# Controller-Board_Rack-PDU_2_0.net
KiCad netlist of a schematic drawn in EAGLE
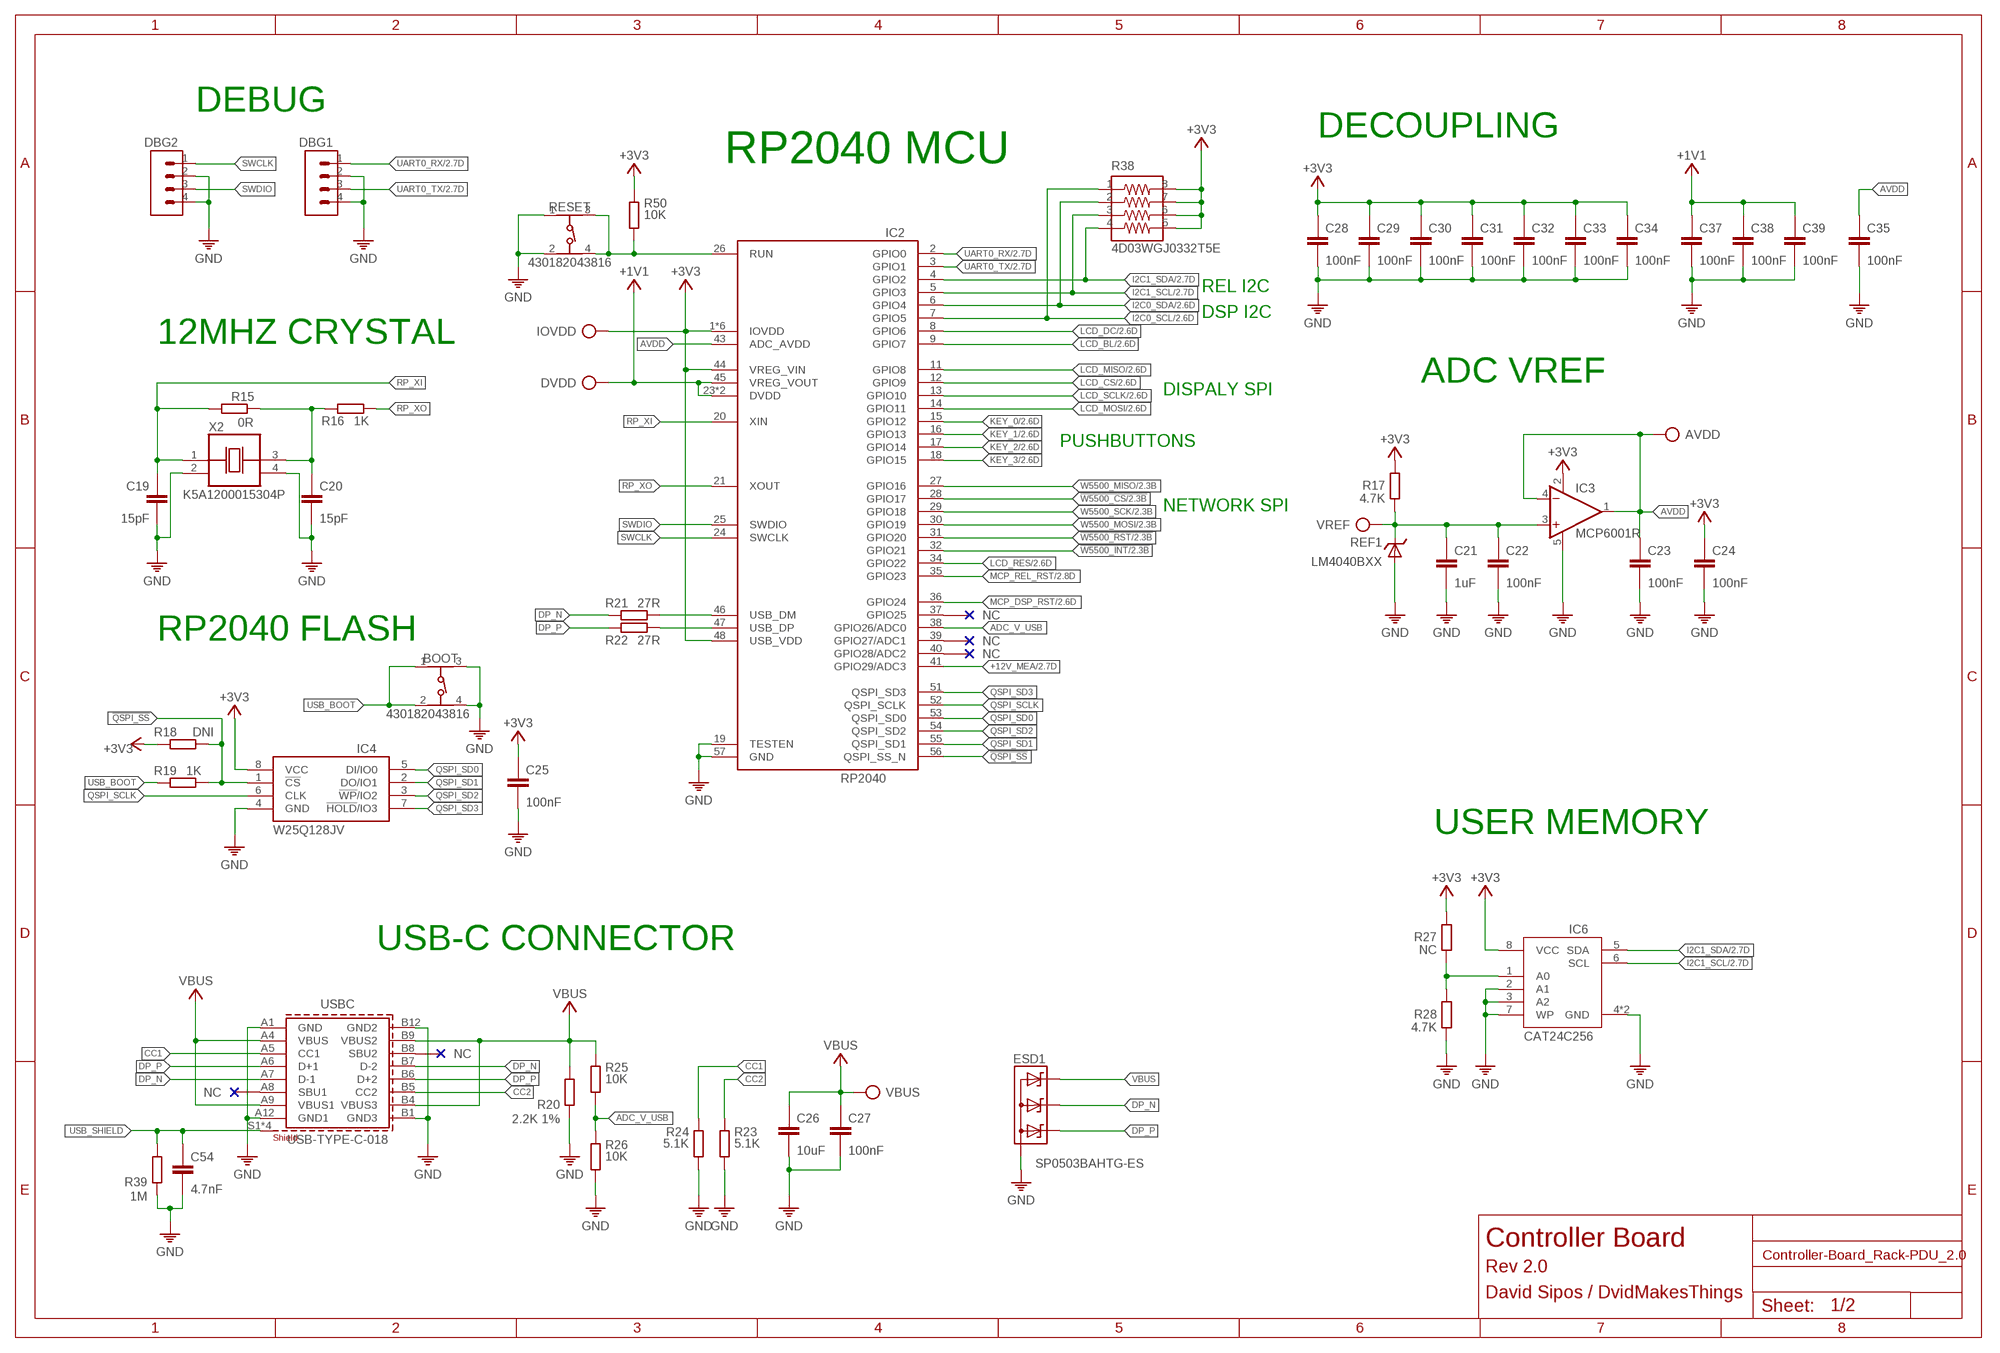
[diagram p0: schematic, sheet 1]
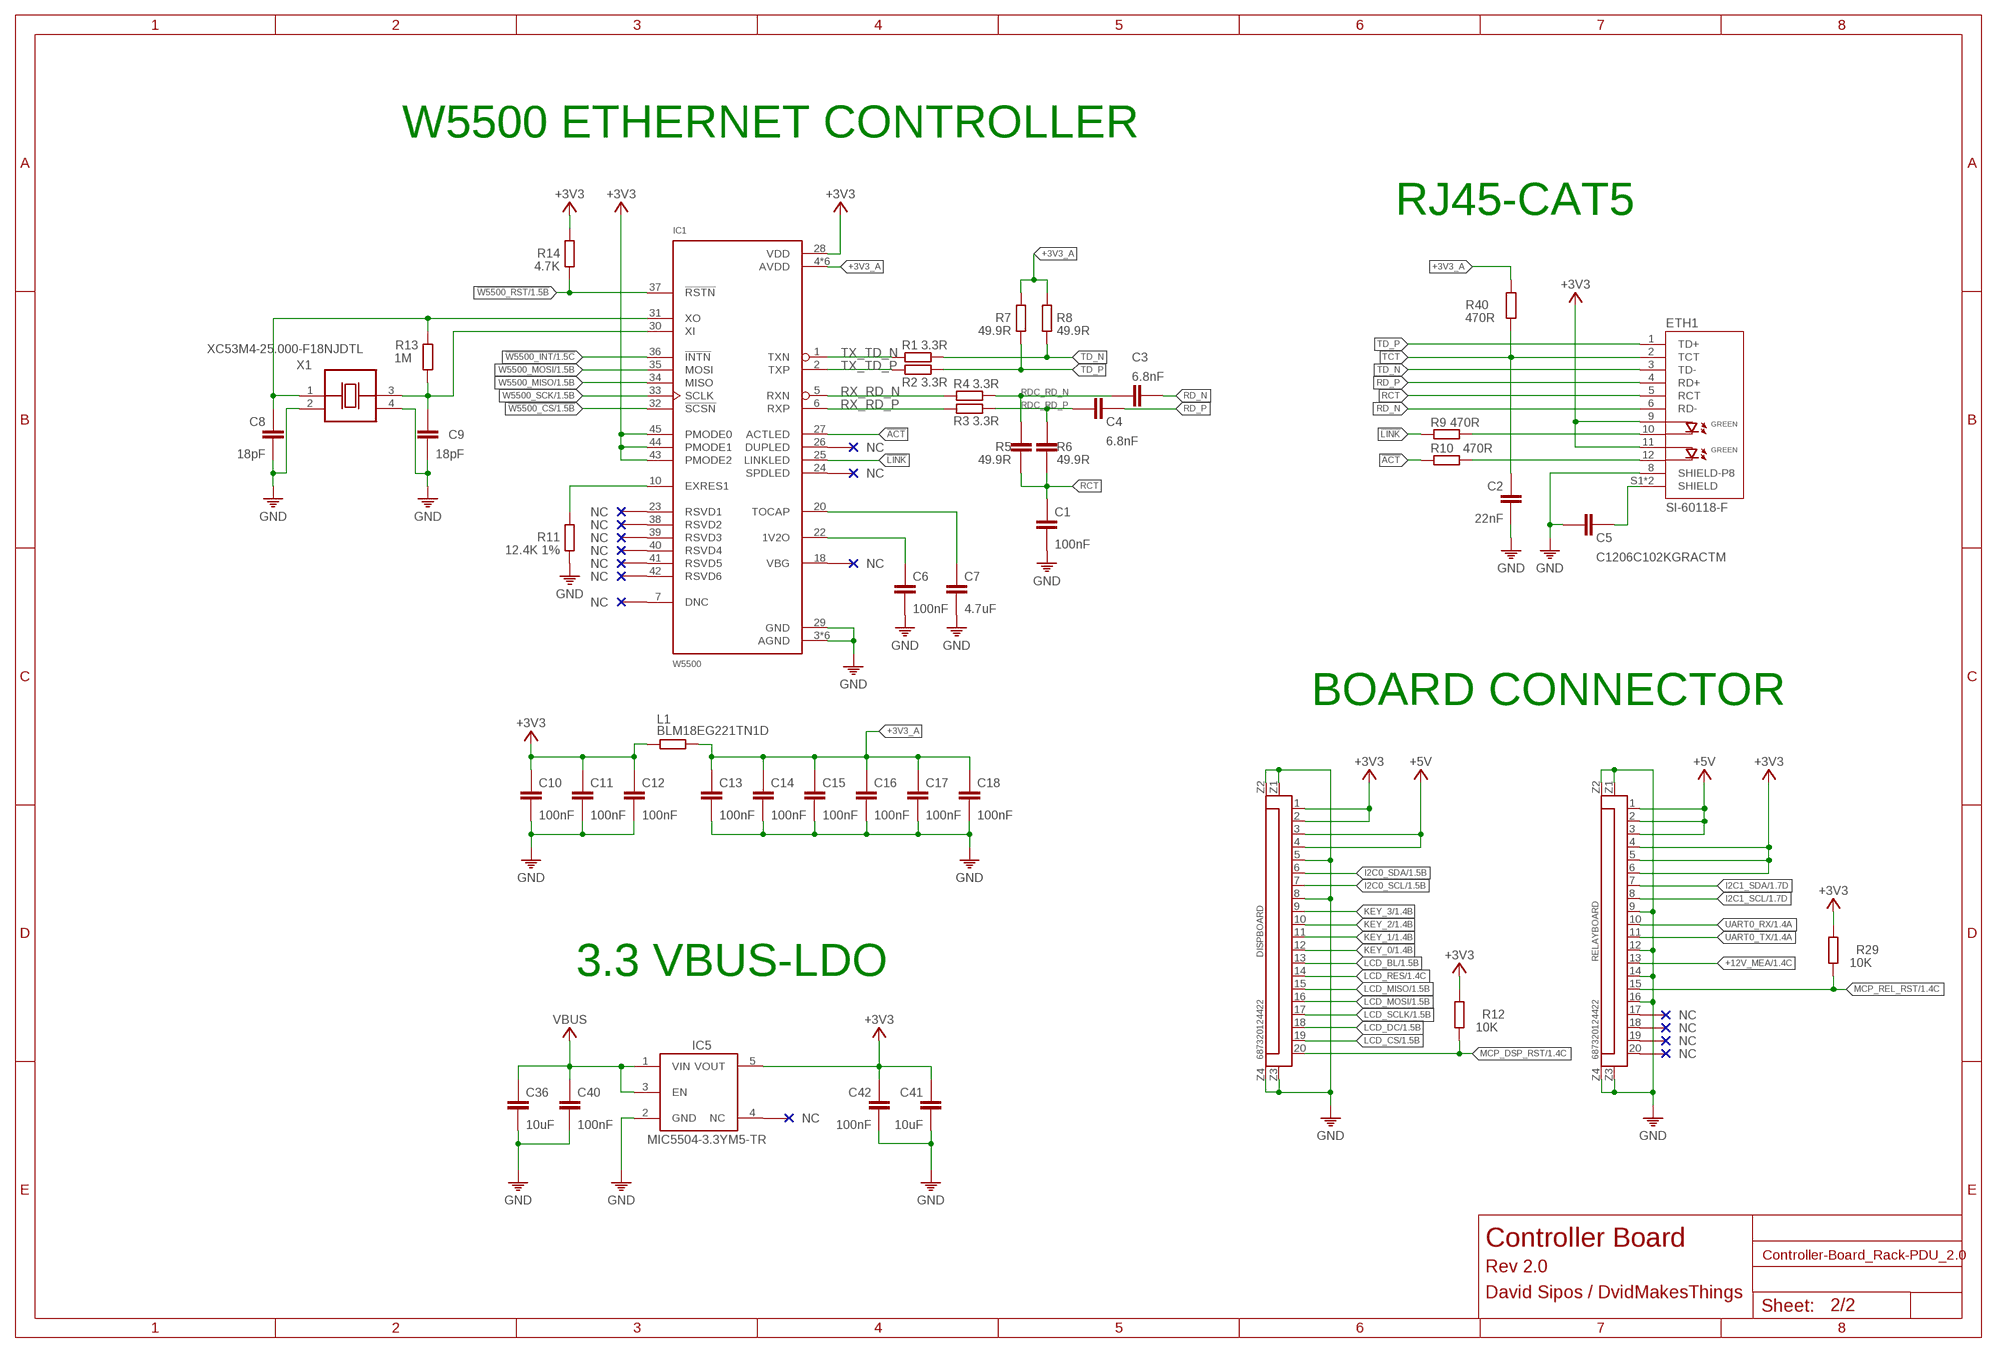
[diagram p1: schematic, sheet 2]

(export (version "E")
  (design (tool "Eeschema 10.0.6"))
  (components
    (comp (ref "AVDD")
      (value "TP")
      (footprint "eagle-import:TP")
      (libsource (lib "eagle-import") (part "TP"))
    )
    (comp (ref "BOOT")
      (value "430182043816")
      (footprint "eagle-import:430182043816")
      (libsource (lib "eagle-import") (part "430182043816"))
    )
    (comp (ref "C19")
      (value "15pF")
      (footprint "eagle-import:C0402")
      (libsource (lib "eagle-import") (part "C-0402"))
    )
    (comp (ref "C20")
      (value "15pF")
      (footprint "eagle-import:C0402")
      (libsource (lib "eagle-import") (part "C-0402"))
    )
    (comp (ref "C21")
      (value "1uF")
      (footprint "eagle-import:C0402")
      (libsource (lib "eagle-import") (part "C-0402"))
    )
    (comp (ref "C22")
      (value "100nF")
      (footprint "eagle-import:C0402")
      (libsource (lib "eagle-import") (part "C-0402"))
    )
    (comp (ref "C23")
      (value "100nF")
      (footprint "eagle-import:C0402")
      (libsource (lib "eagle-import") (part "C-0402"))
    )
    (comp (ref "C24")
      (value "100nF")
      (footprint "eagle-import:C0402")
      (libsource (lib "eagle-import") (part "C-0402"))
    )
    (comp (ref "C25")
      (value "100nF")
      (footprint "eagle-import:C0402")
      (libsource (lib "eagle-import") (part "C-0402"))
    )
    (comp (ref "C26")
      (value "10uF")
      (footprint "eagle-import:0805")
      (libsource (lib "eagle-import") (part "C0805"))
    )
    (comp (ref "C27")
      (value "100nF")
      (footprint "eagle-import:0402")
      (libsource (lib "eagle-import") (part "C0402"))
    )
    (comp (ref "C28")
      (value "100nF")
      (footprint "eagle-import:C0402")
      (libsource (lib "eagle-import") (part "C-0402"))
    )
    (comp (ref "C29")
      (value "100nF")
      (footprint "eagle-import:C0402")
      (libsource (lib "eagle-import") (part "C-0402"))
    )
    (comp (ref "C30")
      (value "100nF")
      (footprint "eagle-import:C0402")
      (libsource (lib "eagle-import") (part "C-0402"))
    )
    (comp (ref "C31")
      (value "100nF")
      (footprint "eagle-import:C0402")
      (libsource (lib "eagle-import") (part "C-0402"))
    )
    (comp (ref "C32")
      (value "100nF")
      (footprint "eagle-import:C0402")
      (libsource (lib "eagle-import") (part "C-0402"))
    )
    (comp (ref "C33")
      (value "100nF")
      (footprint "eagle-import:C0402")
      (libsource (lib "eagle-import") (part "C-0402"))
    )
    (comp (ref "C34")
      (value "100nF")
      (footprint "eagle-import:C0402")
      (libsource (lib "eagle-import") (part "C-0402"))
    )
    (comp (ref "C35")
      (value "100nF")
      (footprint "eagle-import:C0402")
      (libsource (lib "eagle-import") (part "C-0402"))
    )
    (comp (ref "C37")
      (value "100nF")
      (footprint "eagle-import:C0402")
      (libsource (lib "eagle-import") (part "C-0402"))
    )
    (comp (ref "C38")
      (value "100nF")
      (footprint "eagle-import:C0402")
      (libsource (lib "eagle-import") (part "C-0402"))
    )
    (comp (ref "C39")
      (value "100nF")
      (footprint "eagle-import:C0402")
      (libsource (lib "eagle-import") (part "C-0402"))
    )
    (comp (ref "C54")
      (value "4.7nF")
      (footprint "eagle-import:0402")
      (libsource (lib "eagle-import") (part "C0402"))
    )
    (comp (ref "DBG1")
      (value "CON-1X4")
      (footprint "eagle-import:1X4")
      (libsource (lib "eagle-import") (part "CON-1X4"))
    )
    (comp (ref "DBG2")
      (value "CON-1X4")
      (footprint "eagle-import:1X4")
      (libsource (lib "eagle-import") (part "CON-1X4"))
    )
    (comp (ref "DVDD")
      (value "TP")
      (footprint "eagle-import:TP")
      (libsource (lib "eagle-import") (part "TP"))
    )
    (comp (ref "ESD1")
      (value "SP0503BAHTG-ES")
      (footprint "eagle-import:SOT143")
      (libsource (lib "eagle-import") (part "SP0503BAHT"))
    )
    (comp (ref "IC2")
      (value "RP2040")
      (footprint "eagle-import:QFN40P700X700X100-57T510")
      (libsource (lib "eagle-import") (part "RP2040"))
    )
    (comp (ref "IC3")
      (value "MCP6001R")
      (footprint "eagle-import:SOT23-5")
      (libsource (lib "eagle-import") (part "MCP6001RT"))
    )
    (comp (ref "IC4")
      (value "W25Q128JVPIQ")
      (footprint "eagle-import:SON127P600X500X75-8N")
      (libsource (lib "eagle-import") (part "W25Q128JVP"))
    )
    (comp (ref "IC6")
      (value "CAT24C512HU5IGT3")
      (footprint "eagle-import:SON50P300X200X50-9T130X140N")
      (libsource (lib "eagle-import") (part "CAT24C256-HU4"))
    )
    (comp (ref "IOVDD")
      (value "TP")
      (footprint "eagle-import:TP")
      (libsource (lib "eagle-import") (part "TP"))
    )
    (comp (ref "R15")
      (value "0R")
      (footprint "eagle-import:0402")
      (libsource (lib "eagle-import") (part "R0402"))
    )
    (comp (ref "R16")
      (value "1K")
      (footprint "eagle-import:0402")
      (libsource (lib "eagle-import") (part "R0402"))
    )
    (comp (ref "R17")
      (value "4.7K")
      (footprint "eagle-import:0402")
      (libsource (lib "eagle-import") (part "R0402"))
    )
    (comp (ref "R18")
      (value "DNI")
      (footprint "eagle-import:0402")
      (libsource (lib "eagle-import") (part "R0402"))
    )
    (comp (ref "R19")
      (value "1K")
      (footprint "eagle-import:0402")
      (libsource (lib "eagle-import") (part "R0402"))
    )
    (comp (ref "R20")
      (value "2.2K 1%")
      (footprint "eagle-import:0402")
      (libsource (lib "eagle-import") (part "ds_passive_46685041_R0402"))
    )
    (comp (ref "R21")
      (value "27R")
      (footprint "eagle-import:0402")
      (libsource (lib "eagle-import") (part "R0402"))
    )
    (comp (ref "R22")
      (value "27R")
      (footprint "eagle-import:0402")
      (libsource (lib "eagle-import") (part "R0402"))
    )
    (comp (ref "R23")
      (value "5.1K")
      (footprint "eagle-import:0402")
      (libsource (lib "eagle-import") (part "ds_passive_46685041_R0402"))
    )
    (comp (ref "R24")
      (value "5.1K")
      (footprint "eagle-import:0402")
      (libsource (lib "eagle-import") (part "ds_passive_46685041_R0402"))
    )
    (comp (ref "R25")
      (value "10K")
      (footprint "eagle-import:0402")
      (libsource (lib "eagle-import") (part "ds_passive_46685041_R0402"))
    )
    (comp (ref "R26")
      (value "10K")
      (footprint "eagle-import:0402")
      (libsource (lib "eagle-import") (part "ds_passive_46685041_R0402"))
    )
    (comp (ref "R27")
      (value "NC")
      (footprint "eagle-import:0402")
      (libsource (lib "eagle-import") (part "R0402"))
    )
    (comp (ref "R28")
      (value "4.7K")
      (footprint "eagle-import:0402")
      (libsource (lib "eagle-import") (part "R0402"))
    )
    (comp (ref "R38")
      (value "4D03WGJ0332T5E")
      (footprint "eagle-import:742C083103JP")
      (fields
        (field (name "MANUFACTURER") "CTS Resistor Products")
        (field (name "MPN") "742C083103JP")
        (field (name "CREATED_BY") "PCBLayout.com")
      )
      (libsource (lib "eagle-import") (part "742C083103JP"))
    )
    (comp (ref "R39")
      (value "1M")
      (footprint "eagle-import:0402")
      (libsource (lib "eagle-import") (part "ds_passive_46685041_R0402"))
    )
    (comp (ref "R50")
      (value "10K")
      (footprint "eagle-import:0402")
      (libsource (lib "eagle-import") (part "ds_passive_46685041_R0402"))
    )
    (comp (ref "REF1")
      (value "LM4040BXX")
      (footprint "eagle-import:SOT23")
      (libsource (lib "eagle-import") (part "LM4040BXX"))
    )
    (comp (ref "RESET")
      (value "430182043816")
      (footprint "eagle-import:430182043816")
      (libsource (lib "eagle-import") (part "430182043816"))
    )
    (comp (ref "USBC")
      (value "USB-TYPE-C-018")
      (footprint "eagle-import:629722000214")
      (libsource (lib "eagle-import") (part "629722000214"))
    )
    (comp (ref "VBUS")
      (value "TP")
      (footprint "eagle-import:TP")
      (libsource (lib "eagle-import") (part "TP"))
    )
    (comp (ref "VREF")
      (value "TP")
      (footprint "eagle-import:TP")
      (libsource (lib "eagle-import") (part "TP"))
    )
    (comp (ref "X2")
      (value "K5A1200015304P")
      (footprint "eagle-import:OSCCC500X320X130")
      (libsource (lib "eagle-import") (part "CRYSTAL"))
    )
    (comp (ref "C1")
      (value "100nF")
      (footprint "eagle-import:C0402")
      (libsource (lib "eagle-import") (part "C-0402"))
    )
    (comp (ref "C2")
      (value "22nF")
      (footprint "eagle-import:C0402")
      (libsource (lib "eagle-import") (part "C-0402"))
    )
    (comp (ref "C3")
      (value "6.8nF")
      (footprint "eagle-import:C0402")
      (libsource (lib "eagle-import") (part "C-0402"))
    )
    (comp (ref "C4")
      (value "6.8nF")
      (footprint "eagle-import:C0402")
      (libsource (lib "eagle-import") (part "C-0402"))
    )
    (comp (ref "C5")
      (value "C1206C102KGRACTM")
      (footprint "eagle-import:C1206")
      (libsource (lib "eagle-import") (part "C-1206"))
    )
    (comp (ref "C6")
      (value "100nF")
      (footprint "eagle-import:C0402")
      (libsource (lib "eagle-import") (part "C-0402"))
    )
    (comp (ref "C7")
      (value "4.7uF")
      (footprint "eagle-import:C0402")
      (libsource (lib "eagle-import") (part "C-0402"))
    )
    (comp (ref "C8")
      (value "18pF")
      (footprint "eagle-import:C0402")
      (libsource (lib "eagle-import") (part "C-0402"))
    )
    (comp (ref "C9")
      (value "18pF")
      (footprint "eagle-import:C0402")
      (libsource (lib "eagle-import") (part "C-0402"))
    )
    (comp (ref "C10")
      (value "100nF")
      (footprint "eagle-import:C0402")
      (libsource (lib "eagle-import") (part "C-0402"))
    )
    (comp (ref "C11")
      (value "100nF")
      (footprint "eagle-import:C0402")
      (libsource (lib "eagle-import") (part "C-0402"))
    )
    (comp (ref "C12")
      (value "100nF")
      (footprint "eagle-import:C0402")
      (libsource (lib "eagle-import") (part "C-0402"))
    )
    (comp (ref "C13")
      (value "100nF")
      (footprint "eagle-import:C0402")
      (libsource (lib "eagle-import") (part "C-0402"))
    )
    (comp (ref "C14")
      (value "100nF")
      (footprint "eagle-import:C0402")
      (libsource (lib "eagle-import") (part "C-0402"))
    )
    (comp (ref "C15")
      (value "100nF")
      (footprint "eagle-import:C0402")
      (libsource (lib "eagle-import") (part "C-0402"))
    )
    (comp (ref "C16")
      (value "100nF")
      (footprint "eagle-import:C0402")
      (libsource (lib "eagle-import") (part "C-0402"))
    )
    (comp (ref "C17")
      (value "100nF")
      (footprint "eagle-import:C0402")
      (libsource (lib "eagle-import") (part "C-0402"))
    )
    (comp (ref "C18")
      (value "100nF")
      (footprint "eagle-import:C0402")
      (libsource (lib "eagle-import") (part "C-0402"))
    )
    (comp (ref "C36")
      (value "10uF")
      (footprint "eagle-import:0805")
      (libsource (lib "eagle-import") (part "C0805"))
    )
    (comp (ref "C40")
      (value "100nF")
      (footprint "eagle-import:0402")
      (libsource (lib "eagle-import") (part "C0402"))
    )
    (comp (ref "C41")
      (value "10uF")
      (footprint "eagle-import:0805")
      (libsource (lib "eagle-import") (part "C0805"))
    )
    (comp (ref "C42")
      (value "100nF")
      (footprint "eagle-import:0402")
      (libsource (lib "eagle-import") (part "C0402"))
    )
    (comp (ref "DISPBOARD")
      (value "687320124422")
      (footprint "eagle-import:687320124422")
      (libsource (lib "eagle-import") (part "6873XX124422_687320124422"))
    )
    (comp (ref "ETH1")
      (value "SI-60118-F")
      (footprint "eagle-import:RJ45-CAT5")
      (fields (field (name "MANUFACTURER") "Bel Fuse"))
      (libsource (lib "eagle-import") (part "RJ45-CAT5"))
    )
    (comp (ref "IC1")
      (value "W5500")
      (footprint "eagle-import:LQFP48")
      (libsource (lib "eagle-import") (part "W5500"))
    )
    (comp (ref "IC5")
      (value "MIC5504-3.3YM5-TR")
      (footprint "eagle-import:SOT23-5")
      (libsource (lib "eagle-import") (part "MIC5504-3.3YM5-TR"))
    )
    (comp (ref "L1")
      (value "BLM18EG221TN1D")
      (footprint "eagle-import:0603")
      (libsource (lib "eagle-import") (part "R0603"))
    )
    (comp (ref "R1")
      (value "3.3R")
      (footprint "eagle-import:0402")
      (libsource (lib "eagle-import") (part "R0402"))
    )
    (comp (ref "R2")
      (value "3.3R")
      (footprint "eagle-import:0402")
      (libsource (lib "eagle-import") (part "R0402"))
    )
    (comp (ref "R3")
      (value "3.3R")
      (footprint "eagle-import:0402")
      (libsource (lib "eagle-import") (part "R0402"))
    )
    (comp (ref "R4")
      (value "3.3R")
      (footprint "eagle-import:0402")
      (libsource (lib "eagle-import") (part "R0402"))
    )
    (comp (ref "R5")
      (value "49.9R")
      (footprint "eagle-import:C0402")
      (libsource (lib "eagle-import") (part "C-0402"))
    )
    (comp (ref "R6")
      (value "49.9R")
      (footprint "eagle-import:C0402")
      (libsource (lib "eagle-import") (part "C-0402"))
    )
    (comp (ref "R7")
      (value "49.9R")
      (footprint "eagle-import:0402")
      (libsource (lib "eagle-import") (part "R0402"))
    )
    (comp (ref "R8")
      (value "49.9R")
      (footprint "eagle-import:0402")
      (libsource (lib "eagle-import") (part "R0402"))
    )
    (comp (ref "R9")
      (value "470R")
      (footprint "eagle-import:0402")
      (libsource (lib "eagle-import") (part "R0402"))
    )
    (comp (ref "R10")
      (value "470R")
      (footprint "eagle-import:0402")
      (libsource (lib "eagle-import") (part "R0402"))
    )
    (comp (ref "R11")
      (value "12.4K 1%")
      (footprint "eagle-import:0402")
      (libsource (lib "eagle-import") (part "R0402"))
    )
    (comp (ref "R12")
      (value "10K")
      (footprint "eagle-import:0402")
      (libsource (lib "eagle-import") (part "R0402"))
    )
    (comp (ref "R13")
      (value "1M")
      (footprint "eagle-import:0402")
      (libsource (lib "eagle-import") (part "R0402"))
    )
    (comp (ref "R14")
      (value "4.7K")
      (footprint "eagle-import:0402")
      (libsource (lib "eagle-import") (part "R0402"))
    )
    (comp (ref "R29")
      (value "10K")
      (footprint "eagle-import:0402")
      (libsource (lib "eagle-import") (part "R0402"))
    )
    (comp (ref "R40")
      (value "470R")
      (footprint "eagle-import:0402")
      (libsource (lib "eagle-import") (part "R0402"))
    )
    (comp (ref "RELAYBOARD")
      (value "687320124422")
      (footprint "eagle-import:687320124422")
      (libsource (lib "eagle-import") (part "6873XX124422_687320124422"))
    )
    (comp (ref "X1")
      (value "XC53M4-25.000-F18NJDTL")
      (footprint "eagle-import:OSCCC500X320X130")
      (libsource (lib "eagle-import") (part "CRYSTAL"))
    )
  )
  (nets
    (net (code "1") (name "+1V1") (class "Default")
      (node (ref "C37") (pin "1") (pinfunction "1_1") (pintype "passive"))
      (node (ref "C38") (pin "1") (pinfunction "1_1") (pintype "passive"))
      (node (ref "C39") (pin "1") (pinfunction "1_1") (pintype "passive"))
      (node (ref "DVDD") (pin "TP") (pinfunction "P$1_TP") (pintype "bidirectional"))
      (node (ref "IC2") (pin "23") (pinfunction "DVDD_23") (pintype "bidirectional"))
      (node (ref "IC2") (pin "45") (pinfunction "VREG_VOUT_45") (pintype "bidirectional"))
      (node (ref "IC2") (pin "50") (pinfunction "DVDD_50") (pintype "bidirectional"))
    )
    (net (code "2") (name "+3V3") (class "Default")
      (node (ref "C10") (pin "1") (pinfunction "1_1") (pintype "passive"))
      (node (ref "C11") (pin "1") (pinfunction "1_1") (pintype "passive"))
      (node (ref "C12") (pin "1") (pinfunction "1_1") (pintype "passive"))
      (node (ref "C24") (pin "1") (pinfunction "1_1") (pintype "passive"))
      (node (ref "C25") (pin "1") (pinfunction "1_1") (pintype "passive"))
      (node (ref "C28") (pin "1") (pinfunction "1_1") (pintype "passive"))
      (node (ref "C29") (pin "1") (pinfunction "1_1") (pintype "passive"))
      (node (ref "C30") (pin "1") (pinfunction "1_1") (pintype "passive"))
      (node (ref "C31") (pin "1") (pinfunction "1_1") (pintype "passive"))
      (node (ref "C32") (pin "1") (pinfunction "1_1") (pintype "passive"))
      (node (ref "C33") (pin "1") (pinfunction "1_1") (pintype "passive"))
      (node (ref "C34") (pin "1") (pinfunction "1_1") (pintype "passive"))
      (node (ref "C41") (pin "1") (pinfunction "1_1") (pintype "passive"))
      (node (ref "C42") (pin "1") (pinfunction "1_1") (pintype "passive"))
      (node (ref "DISPBOARD") (pin "1") (pinfunction "1_1") (pintype "passive"))
      (node (ref "DISPBOARD") (pin "2") (pinfunction "2_2") (pintype "passive"))
      (node (ref "ETH1") (pin "11") (pinfunction "GA2_11") (pintype "passive"))
      (node (ref "ETH1") (pin "9") (pinfunction "GA1_9") (pintype "passive"))
      (node (ref "IC1") (pin "28") (pinfunction "VDD_28") (pintype "power_in"))
      (node (ref "IC1") (pin "43") (pinfunction "PMODE2_43") (pintype "input"))
      (node (ref "IC1") (pin "44") (pinfunction "PMODE1_44") (pintype "input"))
      (node (ref "IC1") (pin "45") (pinfunction "PMODE0_45") (pintype "input"))
      (node (ref "IC2") (pin "1") (pinfunction "IOVDD_1") (pintype "bidirectional"))
      (node (ref "IC2") (pin "10") (pinfunction "IOVDD_10") (pintype "bidirectional"))
      (node (ref "IC2") (pin "22") (pinfunction "IOVDD_22") (pintype "bidirectional"))
      (node (ref "IC2") (pin "33") (pinfunction "IOVDD_33") (pintype "bidirectional"))
      (node (ref "IC2") (pin "42") (pinfunction "IOVDD_42") (pintype "bidirectional"))
      (node (ref "IC2") (pin "44") (pinfunction "VREG_VIN_44") (pintype "bidirectional"))
      (node (ref "IC2") (pin "48") (pinfunction "USB_VDD_48") (pintype "bidirectional"))
      (node (ref "IC2") (pin "49") (pinfunction "IOVDD_49") (pintype "bidirectional"))
      (node (ref "IC3") (pin "2") (pinfunction "V+_2") (pintype "power_in"))
      (node (ref "IC4") (pin "8") (pinfunction "VCC_8") (pintype "power_in"))
      (node (ref "IC5") (pin "5") (pinfunction "VOUT_5") (pintype "bidirectional"))
      (node (ref "IC6") (pin "8") (pinfunction "VCC_8") (pintype "power_in"))
      (node (ref "IOVDD") (pin "TP") (pinfunction "P$1_TP") (pintype "bidirectional"))
      (node (ref "L1") (pin "1") (pinfunction "1_1") (pintype "passive"))
      (node (ref "R12") (pin "2") (pinfunction "2_2") (pintype "passive"))
      (node (ref "R14") (pin "2") (pinfunction "2_2") (pintype "passive"))
      (node (ref "R17") (pin "2") (pinfunction "2_2") (pintype "passive"))
      (node (ref "R18") (pin "2") (pinfunction "2_2") (pintype "passive"))
      (node (ref "R27") (pin "2") (pinfunction "2_2") (pintype "passive"))
      (node (ref "R29") (pin "2") (pinfunction "2_2") (pintype "passive"))
      (node (ref "R38") (pin "5") (pinfunction "5_5") (pintype "passive"))
      (node (ref "R38") (pin "6") (pinfunction "6_6") (pintype "passive"))
      (node (ref "R38") (pin "7") (pinfunction "7_7") (pintype "passive"))
      (node (ref "R38") (pin "8") (pinfunction "8_8") (pintype "passive"))
      (node (ref "R50") (pin "1") (pinfunction "1_1") (pintype "passive"))
      (node (ref "RELAYBOARD") (pin "4") (pinfunction "4_4") (pintype "passive"))
      (node (ref "RELAYBOARD") (pin "5") (pinfunction "5_5") (pintype "passive"))
      (node (ref "RELAYBOARD") (pin "6") (pinfunction "6_6") (pintype "passive"))
    )
    (net (code "3") (name "+3V3_A") (class "Default")
      (node (ref "C13") (pin "1") (pinfunction "1_1") (pintype "passive"))
      (node (ref "C14") (pin "1") (pinfunction "1_1") (pintype "passive"))
      (node (ref "C15") (pin "1") (pinfunction "1_1") (pintype "passive"))
      (node (ref "C16") (pin "1") (pinfunction "1_1") (pintype "passive"))
      (node (ref "C17") (pin "1") (pinfunction "1_1") (pintype "passive"))
      (node (ref "C18") (pin "1") (pinfunction "1_1") (pintype "passive"))
      (node (ref "IC1") (pin "11") (pinfunction "AVDD_11") (pintype "power_in"))
      (node (ref "IC1") (pin "15") (pinfunction "AVDD_15") (pintype "power_in"))
      (node (ref "IC1") (pin "17") (pinfunction "AVDD_17") (pintype "power_in"))
      (node (ref "IC1") (pin "21") (pinfunction "AVDD_21") (pintype "power_in"))
      (node (ref "IC1") (pin "4") (pinfunction "AVDD_4") (pintype "power_in"))
      (node (ref "IC1") (pin "8") (pinfunction "AVDD_8") (pintype "power_in"))
      (node (ref "L1") (pin "2") (pinfunction "2_2") (pintype "passive"))
      (node (ref "R40") (pin "2") (pinfunction "2_2") (pintype "passive"))
      (node (ref "R7") (pin "2") (pinfunction "2_2") (pintype "passive"))
      (node (ref "R8") (pin "2") (pinfunction "2_2") (pintype "passive"))
    )
    (net (code "4") (name "+5V") (class "Default")
      (node (ref "DISPBOARD") (pin "3") (pinfunction "3_3") (pintype "passive"))
      (node (ref "DISPBOARD") (pin "4") (pinfunction "4_4") (pintype "passive"))
      (node (ref "RELAYBOARD") (pin "1") (pinfunction "1_1") (pintype "passive"))
      (node (ref "RELAYBOARD") (pin "2") (pinfunction "2_2") (pintype "passive"))
      (node (ref "RELAYBOARD") (pin "3") (pinfunction "3_3") (pintype "passive"))
    )
    (net (code "5") (name "+12V_MEA") (class "Default")
      (node (ref "IC2") (pin "41") (pinfunction "GPIO29/ADC3_41") (pintype "bidirectional"))
      (node (ref "RELAYBOARD") (pin "13") (pinfunction "13_13") (pintype "passive"))
    )
    (net (code "6") (name "ADC_V_USB") (class "Default")
      (node (ref "IC2") (pin "38") (pinfunction "GPIO26/ADC0_38") (pintype "bidirectional"))
      (node (ref "R25") (pin "2") (pinfunction "2_2") (pintype "passive"))
      (node (ref "R26") (pin "1") (pinfunction "1_1") (pintype "passive"))
    )
    (net (code "7") (name "AVDD") (class "Default")
      (node (ref "AVDD") (pin "TP") (pinfunction "P$1_TP") (pintype "bidirectional"))
      (node (ref "C23") (pin "1") (pinfunction "1_1") (pintype "passive"))
      (node (ref "C35") (pin "1") (pinfunction "1_1") (pintype "passive"))
      (node (ref "IC2") (pin "43") (pinfunction "ADC_AVDD_43") (pintype "bidirectional"))
      (node (ref "IC3") (pin "1") (pinfunction "OUT_1") (pintype "output"))
      (node (ref "IC3") (pin "4") (pinfunction "-IN_4") (pintype "input"))
    )
    (net (code "8") (name "CC1") (class "Default")
      (node (ref "R24") (pin "1") (pinfunction "1_1") (pintype "passive"))
      (node (ref "USBC") (pin "A5") (pinfunction "CC1_A5") (pintype "passive"))
    )
    (net (code "9") (name "CC2") (class "Default")
      (node (ref "R23") (pin "1") (pinfunction "1_1") (pintype "passive"))
      (node (ref "USBC") (pin "B5") (pinfunction "CC2_B5") (pintype "passive"))
    )
    (net (code "10") (name "DP_N") (class "Default")
      (node (ref "ESD1") (pin "3") (pinfunction "C2_3") (pintype "bidirectional"))
      (node (ref "R21") (pin "1") (pinfunction "1_1") (pintype "passive"))
      (node (ref "USBC") (pin "A7") (pinfunction "D-1_A7") (pintype "passive"))
      (node (ref "USBC") (pin "B7") (pinfunction "D-2_B7") (pintype "passive"))
    )
    (net (code "11") (name "DP_P") (class "Default")
      (node (ref "ESD1") (pin "2") (pinfunction "C1_2") (pintype "bidirectional"))
      (node (ref "R22") (pin "1") (pinfunction "1_1") (pintype "passive"))
      (node (ref "USBC") (pin "A6") (pinfunction "D+1_A6") (pintype "passive"))
      (node (ref "USBC") (pin "B6") (pinfunction "D+2_B6") (pintype "passive"))
    )
    (net (code "12") (name "GND") (class "Default")
      (node (ref "BOOT") (pin "3") (pinfunction "3_3") (pintype "passive"))
      (node (ref "BOOT") (pin "4") (pinfunction "4_4") (pintype "passive"))
      (node (ref "C1") (pin "2") (pinfunction "2_2") (pintype "passive"))
      (node (ref "C10") (pin "2") (pinfunction "2_2") (pintype "passive"))
      (node (ref "C11") (pin "2") (pinfunction "2_2") (pintype "passive"))
      (node (ref "C12") (pin "2") (pinfunction "2_2") (pintype "passive"))
      (node (ref "C13") (pin "2") (pinfunction "2_2") (pintype "passive"))
      (node (ref "C14") (pin "2") (pinfunction "2_2") (pintype "passive"))
      (node (ref "C15") (pin "2") (pinfunction "2_2") (pintype "passive"))
      (node (ref "C16") (pin "2") (pinfunction "2_2") (pintype "passive"))
      (node (ref "C17") (pin "2") (pinfunction "2_2") (pintype "passive"))
      (node (ref "C18") (pin "2") (pinfunction "2_2") (pintype "passive"))
      (node (ref "C19") (pin "2") (pinfunction "2_2") (pintype "passive"))
      (node (ref "C2") (pin "2") (pinfunction "2_2") (pintype "passive"))
      (node (ref "C20") (pin "2") (pinfunction "2_2") (pintype "passive"))
      (node (ref "C21") (pin "2") (pinfunction "2_2") (pintype "passive"))
      (node (ref "C22") (pin "2") (pinfunction "2_2") (pintype "passive"))
      (node (ref "C23") (pin "2") (pinfunction "2_2") (pintype "passive"))
      (node (ref "C24") (pin "2") (pinfunction "2_2") (pintype "passive"))
      (node (ref "C25") (pin "2") (pinfunction "2_2") (pintype "passive"))
      (node (ref "C26") (pin "2") (pinfunction "2_2") (pintype "passive"))
      (node (ref "C27") (pin "2") (pinfunction "2_2") (pintype "passive"))
      (node (ref "C28") (pin "2") (pinfunction "2_2") (pintype "passive"))
      (node (ref "C29") (pin "2") (pinfunction "2_2") (pintype "passive"))
      (node (ref "C30") (pin "2") (pinfunction "2_2") (pintype "passive"))
      (node (ref "C31") (pin "2") (pinfunction "2_2") (pintype "passive"))
      (node (ref "C32") (pin "2") (pinfunction "2_2") (pintype "passive"))
      (node (ref "C33") (pin "2") (pinfunction "2_2") (pintype "passive"))
      (node (ref "C34") (pin "2") (pinfunction "2_2") (pintype "passive"))
      (node (ref "C35") (pin "2") (pinfunction "2_2") (pintype "passive"))
      (node (ref "C36") (pin "2") (pinfunction "2_2") (pintype "passive"))
      (node (ref "C37") (pin "2") (pinfunction "2_2") (pintype "passive"))
      (node (ref "C38") (pin "2") (pinfunction "2_2") (pintype "passive"))
      (node (ref "C39") (pin "2") (pinfunction "2_2") (pintype "passive"))
      (node (ref "C40") (pin "2") (pinfunction "2_2") (pintype "passive"))
      (node (ref "C41") (pin "2") (pinfunction "2_2") (pintype "passive"))
      (node (ref "C42") (pin "2") (pinfunction "2_2") (pintype "passive"))
      (node (ref "C5") (pin "1") (pinfunction "1_1") (pintype "passive"))
      (node (ref "C54") (pin "2") (pinfunction "2_2") (pintype "passive"))
      (node (ref "C6") (pin "2") (pinfunction "2_2") (pintype "passive"))
      (node (ref "C7") (pin "2") (pinfunction "2_2") (pintype "passive"))
      (node (ref "C8") (pin "2") (pinfunction "2_2") (pintype "passive"))
      (node (ref "C9") (pin "2") (pinfunction "2_2") (pintype "passive"))
      (node (ref "DBG1") (pin "2") (pinfunction "P$2_2") (pintype "bidirectional"))
      (node (ref "DBG1") (pin "4") (pinfunction "P$4_4") (pintype "bidirectional"))
      (node (ref "DBG2") (pin "2") (pinfunction "P$2_2") (pintype "bidirectional"))
      (node (ref "DBG2") (pin "4") (pinfunction "P$4_4") (pintype "bidirectional"))
      (node (ref "DISPBOARD") (pin "5") (pinfunction "5_5") (pintype "passive"))
      (node (ref "DISPBOARD") (pin "8") (pinfunction "8_8") (pintype "passive"))
      (node (ref "DISPBOARD") (pin "Z1") (pinfunction "Z1_Z1") (pintype "passive"))
      (node (ref "DISPBOARD") (pin "Z2") (pinfunction "Z2_Z2") (pintype "passive"))
      (node (ref "DISPBOARD") (pin "Z3") (pinfunction "Z3_Z3") (pintype "passive"))
      (node (ref "DISPBOARD") (pin "Z4") (pinfunction "Z4_Z4") (pintype "passive"))
      (node (ref "ESD1") (pin "1") (pinfunction "A_1") (pintype "bidirectional"))
      (node (ref "ETH1") (pin "8") (pinfunction "SHIELD-P8_8") (pintype "passive"))
      (node (ref "IC1") (pin "14") (pinfunction "AGND_14") (pintype "power_in"))
      (node (ref "IC1") (pin "16") (pinfunction "AGND_16") (pintype "power_in"))
      (node (ref "IC1") (pin "19") (pinfunction "AGND_19") (pintype "power_in"))
      (node (ref "IC1") (pin "29") (pinfunction "GND_29") (pintype "passive"))
      (node (ref "IC1") (pin "3") (pinfunction "AGND_3") (pintype "power_in"))
      (node (ref "IC1") (pin "48") (pinfunction "AGND_48") (pintype "power_in"))
      (node (ref "IC1") (pin "9") (pinfunction "AGND_9") (pintype "power_in"))
      (node (ref "IC2") (pin "19") (pinfunction "TESTEN_19") (pintype "bidirectional"))
      (node (ref "IC2") (pin "57") (pinfunction "GND_57") (pintype "bidirectional"))
      (node (ref "IC3") (pin "5") (pinfunction "V-_5") (pintype "power_in"))
      (node (ref "IC4") (pin "4") (pinfunction "GND_4") (pintype "power_in"))
      (node (ref "IC5") (pin "2") (pinfunction "GND_2") (pintype "bidirectional"))
      (node (ref "IC6") (pin "2") (pinfunction "A1_2") (pintype "bidirectional"))
      (node (ref "IC6") (pin "3") (pinfunction "A2_3") (pintype "bidirectional"))
      (node (ref "IC6") (pin "4") (pinfunction "GND_4") (pintype "power_in"))
      (node (ref "IC6") (pin "7") (pinfunction "WP_7") (pintype "bidirectional"))
      (node (ref "IC6") (pin "9") (pinfunction "GND_9") (pintype "power_in"))
      (node (ref "R11") (pin "1") (pinfunction "1_1") (pintype "passive"))
      (node (ref "R20") (pin "2") (pinfunction "2_2") (pintype "passive"))
      (node (ref "R23") (pin "2") (pinfunction "2_2") (pintype "passive"))
      (node (ref "R24") (pin "2") (pinfunction "2_2") (pintype "passive"))
      (node (ref "R26") (pin "2") (pinfunction "2_2") (pintype "passive"))
      (node (ref "R28") (pin "1") (pinfunction "1_1") (pintype "passive"))
      (node (ref "R39") (pin "2") (pinfunction "2_2") (pintype "passive"))
      (node (ref "REF1") (pin "2") (pinfunction "A_2") (pintype "passive"))
      (node (ref "REF1") (pin "3") (pinfunction "A_3") (pintype "passive"))
      (node (ref "RELAYBOARD") (pin "12") (pinfunction "12_12") (pintype "passive"))
      (node (ref "RELAYBOARD") (pin "14") (pinfunction "14_14") (pintype "passive"))
      (node (ref "RELAYBOARD") (pin "16") (pinfunction "16_16") (pintype "passive"))
      (node (ref "RELAYBOARD") (pin "9") (pinfunction "9_9") (pintype "passive"))
      (node (ref "RELAYBOARD") (pin "Z1") (pinfunction "Z1_Z1") (pintype "passive"))
      (node (ref "RELAYBOARD") (pin "Z2") (pinfunction "Z2_Z2") (pintype "passive"))
      (node (ref "RELAYBOARD") (pin "Z3") (pinfunction "Z3_Z3") (pintype "passive"))
      (node (ref "RELAYBOARD") (pin "Z4") (pinfunction "Z4_Z4") (pintype "passive"))
      (node (ref "RESET") (pin "1") (pinfunction "1_1") (pintype "passive"))
      (node (ref "RESET") (pin "2") (pinfunction "2_2") (pintype "passive"))
      (node (ref "USBC") (pin "A1") (pinfunction "GND_A1") (pintype "passive"))
      (node (ref "USBC") (pin "A12") (pinfunction "GND1_A12") (pintype "passive"))
      (node (ref "USBC") (pin "B1") (pinfunction "GND3_B1") (pintype "passive"))
      (node (ref "USBC") (pin "B12") (pinfunction "GND2_B12") (pintype "passive"))
      (node (ref "X1") (pin "2") (pinfunction "VSS_2") (pintype "power_in"))
      (node (ref "X1") (pin "4") (pinfunction "VDD_4") (pintype "power_in"))
      (node (ref "X2") (pin "2") (pinfunction "VSS_2") (pintype "power_in"))
      (node (ref "X2") (pin "4") (pinfunction "VDD_4") (pintype "power_in"))
    )
    (net (code "13") (name "I2C0_SCL") (class "Default")
      (node (ref "DISPBOARD") (pin "7") (pinfunction "7_7") (pintype "passive"))
      (node (ref "IC2") (pin "7") (pinfunction "GPIO5_7") (pintype "bidirectional"))
      (node (ref "R38") (pin "1") (pinfunction "1_1") (pintype "passive"))
    )
    (net (code "14") (name "I2C0_SDA") (class "Default")
      (node (ref "DISPBOARD") (pin "6") (pinfunction "6_6") (pintype "passive"))
      (node (ref "IC2") (pin "6") (pinfunction "GPIO4_6") (pintype "bidirectional"))
      (node (ref "R38") (pin "2") (pinfunction "2_2") (pintype "passive"))
    )
    (net (code "15") (name "I2C1_SCL") (class "Default")
      (node (ref "IC2") (pin "5") (pinfunction "GPIO3_5") (pintype "bidirectional"))
      (node (ref "IC6") (pin "6") (pinfunction "SCL_6") (pintype "bidirectional"))
      (node (ref "R38") (pin "3") (pinfunction "3_3") (pintype "passive"))
      (node (ref "RELAYBOARD") (pin "8") (pinfunction "8_8") (pintype "passive"))
    )
    (net (code "16") (name "I2C1_SDA") (class "Default")
      (node (ref "IC2") (pin "4") (pinfunction "GPIO2_4") (pintype "bidirectional"))
      (node (ref "IC6") (pin "5") (pinfunction "SDA_5") (pintype "bidirectional"))
      (node (ref "R38") (pin "4") (pinfunction "4_4") (pintype "passive"))
      (node (ref "RELAYBOARD") (pin "7") (pinfunction "7_7") (pintype "passive"))
    )
    (net (code "17") (name "KEY_0") (class "Default")
      (node (ref "DISPBOARD") (pin "12") (pinfunction "12_12") (pintype "passive"))
      (node (ref "IC2") (pin "15") (pinfunction "GPIO12_15") (pintype "bidirectional"))
    )
    (net (code "18") (name "KEY_1") (class "Default")
      (node (ref "DISPBOARD") (pin "11") (pinfunction "11_11") (pintype "passive"))
      (node (ref "IC2") (pin "16") (pinfunction "GPIO13_16") (pintype "bidirectional"))
    )
    (net (code "19") (name "KEY_2") (class "Default")
      (node (ref "DISPBOARD") (pin "10") (pinfunction "10_10") (pintype "passive"))
      (node (ref "IC2") (pin "17") (pinfunction "GPIO14_17") (pintype "bidirectional"))
    )
    (net (code "20") (name "KEY_3") (class "Default")
      (node (ref "DISPBOARD") (pin "9") (pinfunction "9_9") (pintype "passive"))
      (node (ref "IC2") (pin "18") (pinfunction "GPIO15_18") (pintype "bidirectional"))
    )
    (net (code "21") (name "LCD_BL") (class "Default")
      (node (ref "DISPBOARD") (pin "13") (pinfunction "13_13") (pintype "passive"))
      (node (ref "IC2") (pin "9") (pinfunction "GPIO7_9") (pintype "bidirectional"))
    )
    (net (code "22") (name "LCD_CS") (class "Default")
      (node (ref "DISPBOARD") (pin "19") (pinfunction "19_19") (pintype "passive"))
      (node (ref "IC2") (pin "12") (pinfunction "GPIO9_12") (pintype "bidirectional"))
    )
    (net (code "23") (name "LCD_DC") (class "Default")
      (node (ref "DISPBOARD") (pin "18") (pinfunction "18_18") (pintype "passive"))
      (node (ref "IC2") (pin "8") (pinfunction "GPIO6_8") (pintype "bidirectional"))
    )
    (net (code "24") (name "LCD_MISO") (class "Default")
      (node (ref "DISPBOARD") (pin "15") (pinfunction "15_15") (pintype "passive"))
      (node (ref "IC2") (pin "11") (pinfunction "GPIO8_11") (pintype "bidirectional"))
    )
    (net (code "25") (name "LCD_MOSI") (class "Default")
      (node (ref "DISPBOARD") (pin "16") (pinfunction "16_16") (pintype "passive"))
      (node (ref "IC2") (pin "14") (pinfunction "GPIO11_14") (pintype "bidirectional"))
    )
    (net (code "26") (name "LCD_RES") (class "Default")
      (node (ref "DISPBOARD") (pin "14") (pinfunction "14_14") (pintype "passive"))
      (node (ref "IC2") (pin "34") (pinfunction "GPIO22_34") (pintype "bidirectional"))
    )
    (net (code "27") (name "LCD_SCLK") (class "Default")
      (node (ref "DISPBOARD") (pin "17") (pinfunction "17_17") (pintype "passive"))
      (node (ref "IC2") (pin "13") (pinfunction "GPIO10_13") (pintype "bidirectional"))
    )
    (net (code "28") (name "MCP_DSP_RST") (class "Default")
      (node (ref "DISPBOARD") (pin "20") (pinfunction "20_20") (pintype "passive"))
      (node (ref "IC2") (pin "36") (pinfunction "GPIO24_36") (pintype "bidirectional"))
      (node (ref "R12") (pin "1") (pinfunction "1_1") (pintype "passive"))
    )
    (net (code "29") (name "MCP_REL_RST") (class "Default")
      (node (ref "IC2") (pin "35") (pinfunction "GPIO23_35") (pintype "bidirectional"))
      (node (ref "R29") (pin "1") (pinfunction "1_1") (pintype "passive"))
      (node (ref "RELAYBOARD") (pin "15") (pinfunction "15_15") (pintype "passive"))
    )
    (net (code "30") (name "Net-(C5-Pad2)") (class "Default")
      (node (ref "C5") (pin "2") (pinfunction "2_2") (pintype "passive"))
      (node (ref "ETH1") (pin "S1") (pinfunction "SHIELD_S1") (pintype "passive"))
      (node (ref "ETH1") (pin "S2") (pinfunction "SHIELD_S2") (pintype "passive"))
    )
    (net (code "31") (name "Net-(ETH1-GK1)") (class "Default")
      (node (ref "ETH1") (pin "10") (pinfunction "GK1_10") (pintype "passive"))
      (node (ref "R9") (pin "2") (pinfunction "2_2") (pintype "passive"))
    )
    (net (code "32") (name "Net-(ETH1-GK2)") (class "Default")
      (node (ref "ETH1") (pin "12") (pinfunction "GK2_12") (pintype "passive"))
      (node (ref "R10") (pin "2") (pinfunction "2_2") (pintype "passive"))
    )
    (net (code "33") (name "Net-(IC1-1V2O)") (class "Default")
      (node (ref "C6") (pin "1") (pinfunction "1_1") (pintype "passive"))
      (node (ref "IC1") (pin "22") (pinfunction "1V2O_22") (pintype "output"))
    )
    (net (code "34") (name "Net-(IC1-EXRES1)") (class "Default")
      (node (ref "IC1") (pin "10") (pinfunction "EXRES1_10") (pintype "bidirectional"))
      (node (ref "R11") (pin "2") (pinfunction "2_2") (pintype "passive"))
    )
    (net (code "35") (name "Net-(IC1-TOCAP)") (class "Default")
      (node (ref "C7") (pin "1") (pinfunction "1_1") (pintype "passive"))
      (node (ref "IC1") (pin "20") (pinfunction "TOCAP_20") (pintype "output"))
    )
    (net (code "36") (name "Net-(IC1-XI)") (class "Default")
      (node (ref "C9") (pin "1") (pinfunction "1_1") (pintype "passive"))
      (node (ref "IC1") (pin "30") (pinfunction "XI_30") (pintype "input"))
      (node (ref "R13") (pin "1") (pinfunction "1_1") (pintype "passive"))
      (node (ref "X1") (pin "3") (pinfunction "OUT_3") (pintype "output"))
    )
    (net (code "37") (name "Net-(IC1-XO)") (class "Default")
      (node (ref "C8") (pin "1") (pinfunction "1_1") (pintype "passive"))
      (node (ref "IC1") (pin "31") (pinfunction "XO_31") (pintype "output"))
      (node (ref "R13") (pin "2") (pinfunction "2_2") (pintype "passive"))
      (node (ref "X1") (pin "1") (pinfunction "CON_1") (pintype "input"))
    )
    (net (code "38") (name "Net-(IC2-RUN)") (class "Default")
      (node (ref "IC2") (pin "26") (pinfunction "RUN_26") (pintype "bidirectional"))
      (node (ref "R50") (pin "2") (pinfunction "2_2") (pintype "passive"))
      (node (ref "RESET") (pin "3") (pinfunction "3_3") (pintype "passive"))
      (node (ref "RESET") (pin "4") (pinfunction "4_4") (pintype "passive"))
    )
    (net (code "39") (name "Net-(IC2-USB_DM)") (class "Default")
      (node (ref "IC2") (pin "46") (pinfunction "USB_DM_46") (pintype "bidirectional"))
      (node (ref "R21") (pin "2") (pinfunction "2_2") (pintype "passive"))
    )
    (net (code "40") (name "Net-(IC2-USB_DP)") (class "Default")
      (node (ref "IC2") (pin "47") (pinfunction "USB_DP_47") (pintype "bidirectional"))
      (node (ref "R22") (pin "2") (pinfunction "2_2") (pintype "passive"))
    )
    (net (code "41") (name "Net-(IC3-+IN)") (class "Default")
      (node (ref "C21") (pin "1") (pinfunction "1_1") (pintype "passive"))
      (node (ref "C22") (pin "1") (pinfunction "1_1") (pintype "passive"))
      (node (ref "IC3") (pin "3") (pinfunction "+IN_3") (pintype "input"))
      (node (ref "R17") (pin "1") (pinfunction "1_1") (pintype "passive"))
      (node (ref "REF1") (pin "1") (pinfunction "C_1") (pintype "passive"))
      (node (ref "VREF") (pin "TP") (pinfunction "P$1_TP") (pintype "bidirectional"))
    )
    (net (code "42") (name "Net-(IC6-A0)") (class "Default")
      (node (ref "IC6") (pin "1") (pinfunction "A0_1") (pintype "bidirectional"))
      (node (ref "R27") (pin "1") (pinfunction "1_1") (pintype "passive"))
      (node (ref "R28") (pin "2") (pinfunction "2_2") (pintype "passive"))
    )
    (net (code "43") (name "Net-(X2-OUT)") (class "Default")
      (node (ref "C20") (pin "1") (pinfunction "1_1") (pintype "passive"))
      (node (ref "R15") (pin "2") (pinfunction "2_2") (pintype "passive"))
      (node (ref "R16") (pin "1") (pinfunction "1_1") (pintype "passive"))
      (node (ref "X2") (pin "3") (pinfunction "OUT_3") (pintype "output"))
    )
    (net (code "44") (name "QSPI_SCLK") (class "Default")
      (node (ref "IC2") (pin "52") (pinfunction "QSPI_SCLK_52") (pintype "bidirectional"))
      (node (ref "IC4") (pin "6") (pinfunction "CLK_6") (pintype "bidirectional"))
    )
    (net (code "45") (name "QSPI_SD0") (class "Default")
      (node (ref "IC2") (pin "53") (pinfunction "QSPI_SD0_53") (pintype "bidirectional"))
      (node (ref "IC4") (pin "5") (pinfunction "DI/IO0_5") (pintype "bidirectional"))
    )
    (net (code "46") (name "QSPI_SD1") (class "Default")
      (node (ref "IC2") (pin "55") (pinfunction "QSPI_SD1_55") (pintype "bidirectional"))
      (node (ref "IC4") (pin "2") (pinfunction "DO/IO1_2") (pintype "bidirectional"))
    )
    (net (code "47") (name "QSPI_SD2") (class "Default")
      (node (ref "IC2") (pin "54") (pinfunction "QSPI_SD2_54") (pintype "bidirectional"))
      (node (ref "IC4") (pin "3") (pinfunction "~{WP}/IO2_3") (pintype "bidirectional"))
    )
    (net (code "48") (name "QSPI_SD3") (class "Default")
      (node (ref "IC2") (pin "51") (pinfunction "QSPI_SD3_51") (pintype "bidirectional"))
      (node (ref "IC4") (pin "7") (pinfunction "~{HOLD}/IO3_7") (pintype "bidirectional"))
    )
    (net (code "49") (name "RCT") (class "Default")
      (node (ref "C1") (pin "1") (pinfunction "1_1") (pintype "passive"))
      (node (ref "ETH1") (pin "5") (pinfunction "RCT_5") (pintype "passive"))
      (node (ref "R5") (pin "1") (pinfunction "1_1") (pintype "passive"))
      (node (ref "R6") (pin "1") (pinfunction "1_1") (pintype "passive"))
    )
    (net (code "50") (name "RDC_RD_N") (class "Default")
      (node (ref "C3") (pin "1") (pinfunction "1_1") (pintype "passive"))
      (node (ref "R4") (pin "2") (pinfunction "2_2") (pintype "passive"))
      (node (ref "R5") (pin "2") (pinfunction "2_2") (pintype "passive"))
    )
    (net (code "51") (name "RDC_RD_P") (class "Default")
      (node (ref "C4") (pin "1") (pinfunction "1_1") (pintype "passive"))
      (node (ref "R3") (pin "2") (pinfunction "2_2") (pintype "passive"))
      (node (ref "R6") (pin "2") (pinfunction "2_2") (pintype "passive"))
    )
    (net (code "52") (name "RD_N") (class "Default")
      (node (ref "C3") (pin "2") (pinfunction "2_2") (pintype "passive"))
      (node (ref "ETH1") (pin "6") (pinfunction "RD-_6") (pintype "passive"))
    )
    (net (code "53") (name "RD_P") (class "Default")
      (node (ref "C4") (pin "2") (pinfunction "2_2") (pintype "passive"))
      (node (ref "ETH1") (pin "4") (pinfunction "RD+_4") (pintype "passive"))
    )
    (net (code "54") (name "RP_XI") (class "Default")
      (node (ref "C19") (pin "1") (pinfunction "1_1") (pintype "passive"))
      (node (ref "IC2") (pin "20") (pinfunction "XIN_20") (pintype "bidirectional"))
      (node (ref "R15") (pin "1") (pinfunction "1_1") (pintype "passive"))
      (node (ref "X2") (pin "1") (pinfunction "CON_1") (pintype "input"))
    )
    (net (code "55") (name "RP_XO") (class "Default")
      (node (ref "IC2") (pin "21") (pinfunction "XOUT_21") (pintype "bidirectional"))
      (node (ref "R16") (pin "2") (pinfunction "2_2") (pintype "passive"))
    )
    (net (code "56") (name "RX_RD_N") (class "Default")
      (node (ref "IC1") (pin "5") (pinfunction "RXN_5") (pintype "input"))
      (node (ref "R4") (pin "1") (pinfunction "1_1") (pintype "passive"))
    )
    (net (code "57") (name "RX_RD_P") (class "Default")
      (node (ref "IC1") (pin "6") (pinfunction "RXP_6") (pintype "input"))
      (node (ref "R3") (pin "1") (pinfunction "1_1") (pintype "passive"))
    )
    (net (code "58") (name "SWCLK") (class "Default")
      (node (ref "DBG2") (pin "1") (pinfunction "P$1_1") (pintype "bidirectional"))
      (node (ref "IC2") (pin "24") (pinfunction "SWCLK_24") (pintype "bidirectional"))
    )
    (net (code "59") (name "SWDIO") (class "Default")
      (node (ref "DBG2") (pin "3") (pinfunction "P$3_3") (pintype "bidirectional"))
      (node (ref "IC2") (pin "25") (pinfunction "SWDIO_25") (pintype "bidirectional"))
    )
    (net (code "60") (name "TCT") (class "Default")
      (node (ref "C2") (pin "1") (pinfunction "1_1") (pintype "passive"))
      (node (ref "ETH1") (pin "2") (pinfunction "TCT_2") (pintype "passive"))
      (node (ref "R40") (pin "1") (pinfunction "1_1") (pintype "passive"))
    )
    (net (code "61") (name "TD_N") (class "Default")
      (node (ref "ETH1") (pin "3") (pinfunction "TD-_3") (pintype "passive"))
      (node (ref "R1") (pin "2") (pinfunction "2_2") (pintype "passive"))
      (node (ref "R8") (pin "1") (pinfunction "1_1") (pintype "passive"))
    )
    (net (code "62") (name "TD_P") (class "Default")
      (node (ref "ETH1") (pin "1") (pinfunction "TD+_1") (pintype "passive"))
      (node (ref "R2") (pin "2") (pinfunction "2_2") (pintype "passive"))
      (node (ref "R7") (pin "1") (pinfunction "1_1") (pintype "passive"))
    )
    (net (code "63") (name "TX_TD_N") (class "Default")
      (node (ref "IC1") (pin "1") (pinfunction "TXN_1") (pintype "output"))
      (node (ref "R1") (pin "1") (pinfunction "1_1") (pintype "passive"))
    )
    (net (code "64") (name "TX_TD_P") (class "Default")
      (node (ref "IC1") (pin "2") (pinfunction "TXP_2") (pintype "output"))
      (node (ref "R2") (pin "1") (pinfunction "1_1") (pintype "passive"))
    )
    (net (code "65") (name "UART0_RX") (class "Default")
      (node (ref "DBG1") (pin "1") (pinfunction "P$1_1") (pintype "bidirectional"))
      (node (ref "IC2") (pin "2") (pinfunction "GPIO0_2") (pintype "bidirectional"))
      (node (ref "RELAYBOARD") (pin "10") (pinfunction "10_10") (pintype "passive"))
    )
    (net (code "66") (name "UART0_TX") (class "Default")
      (node (ref "DBG1") (pin "3") (pinfunction "P$3_3") (pintype "bidirectional"))
      (node (ref "IC2") (pin "3") (pinfunction "GPIO1_3") (pintype "bidirectional"))
      (node (ref "RELAYBOARD") (pin "11") (pinfunction "11_11") (pintype "passive"))
    )
    (net (code "67") (name "USB_BOOT") (class "Default")
      (node (ref "BOOT") (pin "1") (pinfunction "1_1") (pintype "passive"))
      (node (ref "BOOT") (pin "2") (pinfunction "2_2") (pintype "passive"))
      (node (ref "R19") (pin "1") (pinfunction "1_1") (pintype "passive"))
    )
    (net (code "68") (name "USB_SHIELD") (class "Default")
      (node (ref "C54") (pin "1") (pinfunction "1_1") (pintype "passive"))
      (node (ref "R39") (pin "1") (pinfunction "1_1") (pintype "passive"))
      (node (ref "USBC") (pin "S1") (pinfunction "SHIELD_S1") (pintype "passive"))
      (node (ref "USBC") (pin "S2") (pinfunction "SHIELD_S2") (pintype "passive"))
      (node (ref "USBC") (pin "S3") (pinfunction "SHIELD_S3") (pintype "passive"))
      (node (ref "USBC") (pin "S4") (pinfunction "SHIELD_S4") (pintype "passive"))
    )
    (net (code "69") (name "VBUS") (class "Default")
      (node (ref "C26") (pin "1") (pinfunction "1_1") (pintype "passive"))
      (node (ref "C27") (pin "1") (pinfunction "1_1") (pintype "passive"))
      (node (ref "C36") (pin "1") (pinfunction "1_1") (pintype "passive"))
      (node (ref "C40") (pin "1") (pinfunction "1_1") (pintype "passive"))
      (node (ref "ESD1") (pin "4") (pinfunction "C3_4") (pintype "bidirectional"))
      (node (ref "IC5") (pin "1") (pinfunction "VIN_1") (pintype "bidirectional"))
      (node (ref "IC5") (pin "3") (pinfunction "EN_3") (pintype "bidirectional"))
      (node (ref "R20") (pin "1") (pinfunction "1_1") (pintype "passive"))
      (node (ref "R25") (pin "1") (pinfunction "1_1") (pintype "passive"))
      (node (ref "USBC") (pin "A4") (pinfunction "VBUS_A4") (pintype "passive"))
      (node (ref "USBC") (pin "A9") (pinfunction "VBUS1_A9") (pintype "passive"))
      (node (ref "USBC") (pin "B4") (pinfunction "VBUS3_B4") (pintype "passive"))
      (node (ref "USBC") (pin "B9") (pinfunction "VBUS2_B9") (pintype "passive"))
      (node (ref "VBUS") (pin "TP") (pinfunction "P$1_TP") (pintype "bidirectional"))
    )
    (net (code "70") (name "W5500_MISO") (class "Default")
      (node (ref "IC1") (pin "34") (pinfunction "MISO_34") (pintype "output"))
      (node (ref "IC2") (pin "27") (pinfunction "GPIO16_27") (pintype "bidirectional"))
    )
    (net (code "71") (name "W5500_MOSI") (class "Default")
      (node (ref "IC1") (pin "35") (pinfunction "MOSI_35") (pintype "input"))
      (node (ref "IC2") (pin "30") (pinfunction "GPIO19_30") (pintype "bidirectional"))
    )
    (net (code "72") (name "W5500_SCK") (class "Default")
      (node (ref "IC1") (pin "33") (pinfunction "SCLK_33") (pintype "input"))
      (node (ref "IC2") (pin "29") (pinfunction "GPIO18_29") (pintype "bidirectional"))
    )
    (net (code "73") (name "unconnected-(IC1-DNC-Pad7)") (class "Default")
      (node (ref "IC1") (pin "7") (pinfunction "DNC_7") (pintype "bidirectional"))
    )
    (net (code "74") (name "unconnected-(IC1-DUPLED-Pad26)") (class "Default")
      (node (ref "IC1") (pin "26") (pinfunction "DUPLED_26") (pintype "output"))
    )
    (net (code "75") (name "unconnected-(IC1-RSVD1-Pad23)") (class "Default")
      (node (ref "IC1") (pin "23") (pinfunction "RSVD1_23") (pintype "input"))
    )
    (net (code "76") (name "unconnected-(IC1-RSVD2-Pad38)") (class "Default")
      (node (ref "IC1") (pin "38") (pinfunction "RSVD2_38") (pintype "input"))
    )
    (net (code "77") (name "unconnected-(IC1-RSVD3-Pad39)") (class "Default")
      (node (ref "IC1") (pin "39") (pinfunction "RSVD3_39") (pintype "input"))
    )
    (net (code "78") (name "unconnected-(IC1-RSVD4-Pad40)") (class "Default")
      (node (ref "IC1") (pin "40") (pinfunction "RSVD4_40") (pintype "input"))
    )
    (net (code "79") (name "unconnected-(IC1-RSVD5-Pad41)") (class "Default")
      (node (ref "IC1") (pin "41") (pinfunction "RSVD5_41") (pintype "input"))
    )
    (net (code "80") (name "unconnected-(IC1-RSVD6-Pad42)") (class "Default")
      (node (ref "IC1") (pin "42") (pinfunction "RSVD6_42") (pintype "input"))
    )
    (net (code "81") (name "unconnected-(IC1-SPDLED-Pad24)") (class "Default")
      (node (ref "IC1") (pin "24") (pinfunction "SPDLED_24") (pintype "output"))
    )
    (net (code "82") (name "unconnected-(IC1-VBG-Pad18)") (class "Default")
      (node (ref "IC1") (pin "18") (pinfunction "VBG_18") (pintype "output"))
    )
    (net (code "83") (name "unconnected-(IC2-GPIO25-Pad37)") (class "Default")
      (node (ref "IC2") (pin "37") (pinfunction "GPIO25_37") (pintype "bidirectional"))
    )
    (net (code "84") (name "unconnected-(IC2-GPIO27{slash}ADC1-Pad39)") (class "Default")
      (node (ref "IC2") (pin "39") (pinfunction "GPIO27/ADC1_39") (pintype "bidirectional"))
    )
    (net (code "85") (name "unconnected-(IC2-GPIO28{slash}ADC2-Pad40)") (class "Default")
      (node (ref "IC2") (pin "40") (pinfunction "GPIO28/ADC2_40") (pintype "bidirectional"))
    )
    (net (code "86") (name "unconnected-(IC5-NC-Pad4)") (class "Default")
      (node (ref "IC5") (pin "4") (pinfunction "NC_4") (pintype "bidirectional"))
    )
    (net (code "87") (name "unconnected-(RELAYBOARD-Pad17)") (class "Default")
      (node (ref "RELAYBOARD") (pin "17") (pinfunction "17_17") (pintype "passive"))
    )
    (net (code "88") (name "unconnected-(RELAYBOARD-Pad18)") (class "Default")
      (node (ref "RELAYBOARD") (pin "18") (pinfunction "18_18") (pintype "passive"))
    )
    (net (code "89") (name "unconnected-(RELAYBOARD-Pad19)") (class "Default")
      (node (ref "RELAYBOARD") (pin "19") (pinfunction "19_19") (pintype "passive"))
    )
    (net (code "90") (name "unconnected-(RELAYBOARD-Pad20)") (class "Default")
      (node (ref "RELAYBOARD") (pin "20") (pinfunction "20_20") (pintype "passive"))
    )
    (net (code "91") (name "unconnected-(USBC-SBU1-PadA8)") (class "Default")
      (node (ref "USBC") (pin "A8") (pinfunction "SBU1_A8") (pintype "passive"))
    )
    (net (code "92") (name "unconnected-(USBC-SBU2-PadB8)") (class "Default")
      (node (ref "USBC") (pin "B8") (pinfunction "SBU2_B8") (pintype "passive"))
    )
    (net (code "93") (name "~{ACT}") (class "Default")
      (node (ref "IC1") (pin "27") (pinfunction "ACTLED_27") (pintype "output"))
      (node (ref "R10") (pin "1") (pinfunction "1_1") (pintype "passive"))
    )
    (net (code "94") (name "~{LINK}") (class "Default")
      (node (ref "IC1") (pin "25") (pinfunction "LINKLED_25") (pintype "output"))
      (node (ref "R9") (pin "1") (pinfunction "1_1") (pintype "passive"))
    )
    (net (code "95") (name "~{QSPI_SS}") (class "Default")
      (node (ref "IC2") (pin "56") (pinfunction "QSPI_SS_N_56") (pintype "bidirectional"))
      (node (ref "IC4") (pin "1") (pinfunction "~{CS}_1") (pintype "bidirectional"))
      (node (ref "R18") (pin "1") (pinfunction "1_1") (pintype "passive"))
      (node (ref "R19") (pin "2") (pinfunction "2_2") (pintype "passive"))
    )
    (net (code "96") (name "~{W5500_CS}") (class "Default")
      (node (ref "IC1") (pin "32") (pinfunction "~{SCSN}_32") (pintype "input"))
      (node (ref "IC2") (pin "28") (pinfunction "GPIO17_28") (pintype "bidirectional"))
    )
    (net (code "97") (name "~{W5500_INT}") (class "Default")
      (node (ref "IC1") (pin "36") (pinfunction "~{INTN}_36") (pintype "input"))
      (node (ref "IC2") (pin "32") (pinfunction "GPIO21_32") (pintype "bidirectional"))
    )
    (net (code "98") (name "~{W5500_RST}") (class "Default")
      (node (ref "IC1") (pin "37") (pinfunction "~{RSTN}_37") (pintype "input"))
      (node (ref "IC2") (pin "31") (pinfunction "GPIO20_31") (pintype "bidirectional"))
      (node (ref "R14") (pin "1") (pinfunction "1_1") (pintype "passive"))
    )
  )
)
